# miranda_hector_115clock-6.net
KiCad netlist of a schematic drawn in EAGLE
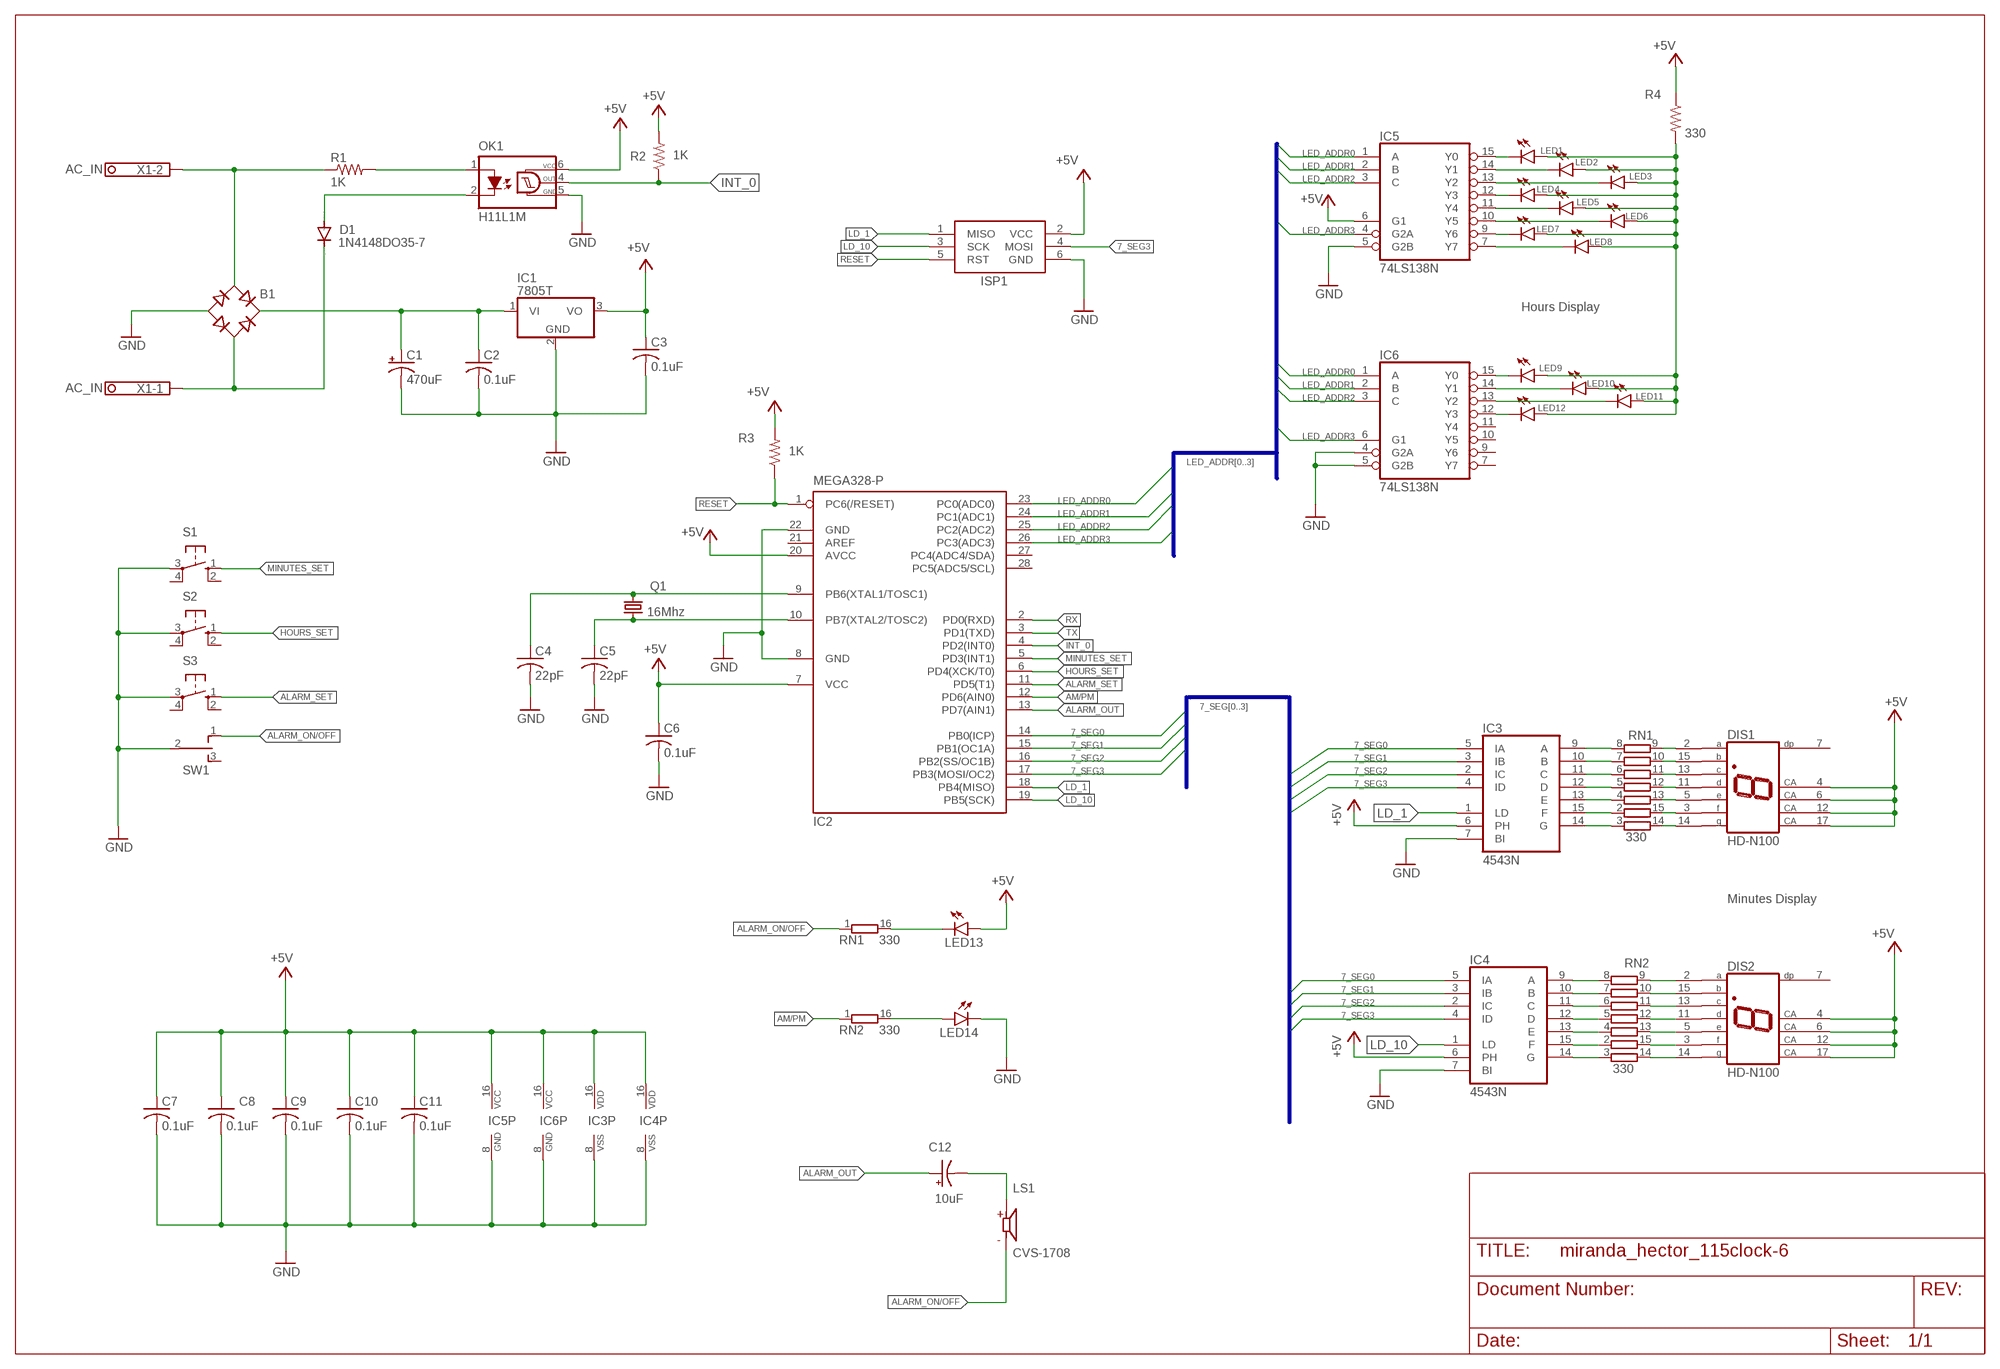
[diagram p0: schematic, sheet 1]

(export (version "E")
  (design (tool "Eeschema 10.0.6"))
  (components
    (comp (ref "B1")
      (value "B-DIL")
      (footprint "eagle-import:B-DIL")
      (libsource (lib "eagle-import") (part "B-DIL"))
    )
    (comp (ref "C1")
      (value "470uF")
      (footprint "eagle-import:E3,5-8")
      (libsource (lib "eagle-import") (part "CPOL-USE3.5-8"))
    )
    (comp (ref "C2")
      (value "0.1uF")
      (footprint "eagle-import:C025-025X050")
      (libsource (lib "eagle-import") (part "C-US025-025X050"))
    )
    (comp (ref "C3")
      (value "0.1uF")
      (footprint "eagle-import:C025-025X050")
      (libsource (lib "eagle-import") (part "C-US025-025X050"))
    )
    (comp (ref "C4")
      (value "22pF")
      (footprint "eagle-import:C025-025X050")
      (libsource (lib "eagle-import") (part "C-US025-025X050"))
    )
    (comp (ref "C5")
      (value "22pF")
      (footprint "eagle-import:C025-025X050")
      (libsource (lib "eagle-import") (part "C-US025-025X050"))
    )
    (comp (ref "C6")
      (value "0.1uF")
      (footprint "eagle-import:C025-025X050")
      (libsource (lib "eagle-import") (part "C-US025-025X050"))
    )
    (comp (ref "C7")
      (value "0.1uF")
      (footprint "eagle-import:C025-025X050")
      (libsource (lib "eagle-import") (part "C-US025-025X050"))
    )
    (comp (ref "C8")
      (value "0.1uF")
      (footprint "eagle-import:C025-025X050")
      (libsource (lib "eagle-import") (part "C-US025-025X050"))
    )
    (comp (ref "C9")
      (value "0.1uF")
      (footprint "eagle-import:C025-025X050")
      (libsource (lib "eagle-import") (part "C-US025-025X050"))
    )
    (comp (ref "C10")
      (value "0.1uF")
      (footprint "eagle-import:C025-025X050")
      (libsource (lib "eagle-import") (part "C-US025-025X050"))
    )
    (comp (ref "C11")
      (value "0.1uF")
      (footprint "eagle-import:C025-025X050")
      (libsource (lib "eagle-import") (part "C-US025-025X050"))
    )
    (comp (ref "C12")
      (value "10uF")
      (footprint "eagle-import:E2,5-6E")
      (libsource (lib "eagle-import") (part "CPOL-USE2,5-6E"))
    )
    (comp (ref "D1")
      (value "1N4148DO35-7")
      (footprint "eagle-import:DO35-7")
      (libsource (lib "eagle-import") (part "1N4148DO35-7"))
    )
    (comp (ref "DIS1")
      (value "HD-N100")
      (footprint "eagle-import:HDSP-Q")
      (libsource (lib "eagle-import") (part "HD-N100"))
    )
    (comp (ref "DIS2")
      (value "HD-N100")
      (footprint "eagle-import:HDSP-Q")
      (libsource (lib "eagle-import") (part "HD-N100"))
    )
    (comp (ref "IC1")
      (value "7805T")
      (footprint "eagle-import:TO220H")
      (libsource (lib "eagle-import") (part "78T05"))
    )
    (comp (ref "IC2")
      (value "MEGA328-P")
      (footprint "eagle-import:DIL28-3")
      (libsource (lib "eagle-import") (part "MEGA8-P"))
    )
    (comp (ref "IC3")
      (value "4543N")
      (footprint "eagle-import:DIL16")
      (libsource (lib "eagle-import") (part "4543N"))
    )
    (comp (ref "IC4")
      (value "4543N")
      (footprint "eagle-import:DIL16")
      (libsource (lib "eagle-import") (part "4543N"))
    )
    (comp (ref "IC5")
      (value "74LS138N")
      (footprint "eagle-import:DIL16")
      (libsource (lib "eagle-import") (part "74138NLS"))
    )
    (comp (ref "IC6")
      (value "74LS138N")
      (footprint "eagle-import:DIL16")
      (libsource (lib "eagle-import") (part "74138NLS"))
    )
    (comp (ref "ISP1")
      (value "AVRISP-6")
      (footprint "eagle-import:AVRISP")
      (libsource (lib "eagle-import") (part "AVRISP-6"))
    )
    (comp (ref "LED1")
      (value "LED10MM")
      (footprint "eagle-import:LED10MM")
      (libsource (lib "eagle-import") (part "LED10MM"))
    )
    (comp (ref "LED2")
      (value "LED10MM")
      (footprint "eagle-import:LED10MM")
      (libsource (lib "eagle-import") (part "LED10MM"))
    )
    (comp (ref "LED3")
      (value "LED10MM")
      (footprint "eagle-import:LED10MM")
      (libsource (lib "eagle-import") (part "LED10MM"))
    )
    (comp (ref "LED4")
      (value "LED10MM")
      (footprint "eagle-import:LED10MM")
      (libsource (lib "eagle-import") (part "LED10MM"))
    )
    (comp (ref "LED5")
      (value "LED10MM")
      (footprint "eagle-import:LED10MM")
      (libsource (lib "eagle-import") (part "LED10MM"))
    )
    (comp (ref "LED6")
      (value "LED10MM")
      (footprint "eagle-import:LED10MM")
      (libsource (lib "eagle-import") (part "LED10MM"))
    )
    (comp (ref "LED7")
      (value "LED10MM")
      (footprint "eagle-import:LED10MM")
      (libsource (lib "eagle-import") (part "LED10MM"))
    )
    (comp (ref "LED8")
      (value "LED10MM")
      (footprint "eagle-import:LED10MM")
      (libsource (lib "eagle-import") (part "LED10MM"))
    )
    (comp (ref "LED9")
      (value "LED10MM")
      (footprint "eagle-import:LED10MM")
      (libsource (lib "eagle-import") (part "LED10MM"))
    )
    (comp (ref "LED10")
      (value "LED10MM")
      (footprint "eagle-import:LED10MM")
      (libsource (lib "eagle-import") (part "LED10MM"))
    )
    (comp (ref "LED11")
      (value "LED10MM")
      (footprint "eagle-import:LED10MM")
      (libsource (lib "eagle-import") (part "LED10MM"))
    )
    (comp (ref "LED12")
      (value "LED10MM")
      (footprint "eagle-import:LED10MM")
      (libsource (lib "eagle-import") (part "LED10MM"))
    )
    (comp (ref "LED13")
      (value "LED5MM")
      (footprint "eagle-import:LED5MM")
      (libsource (lib "eagle-import") (part "LED5MM"))
    )
    (comp (ref "LED14")
      (value "LED5MM")
      (footprint "eagle-import:LED5MM")
      (libsource (lib "eagle-import") (part "LED5MM"))
    )
    (comp (ref "LS1")
      (value "CVS-1708")
      (footprint "eagle-import:SPKR_CVS-1708")
      (fields (field (name "MF") "CUI"))
      (libsource (lib "eagle-import") (part "CVS-1708"))
    )
    (comp (ref "OK1")
      (value "H11L1M")
      (footprint "eagle-import:DIL06")
      (fields (field (name "MF") "FAIRCHILD SEMICONDUCTOR") (field (name "MPN") "H11L1-M"))
      (libsource (lib "eagle-import") (part "H11LM1"))
    )
    (comp (ref "Q1")
      (value "16Mhz")
      (footprint "eagle-import:HC49_S")
      (libsource (lib "eagle-import") (part "CRYSTALHC49S"))
    )
    (comp (ref "R1")
      (value "1K")
      (footprint "eagle-import:0204_7")
      (libsource (lib "eagle-import") (part "R-US_0204/7"))
    )
    (comp (ref "R2")
      (value "1K")
      (footprint "eagle-import:0204_7")
      (libsource (lib "eagle-import") (part "R-US_0204/7"))
    )
    (comp (ref "R3")
      (value "1K")
      (footprint "eagle-import:0204_7")
      (libsource (lib "eagle-import") (part "R-US_0204/7"))
    )
    (comp (ref "R4")
      (value "330")
      (footprint "eagle-import:0204_7")
      (libsource (lib "eagle-import") (part "R-US_0204/7"))
    )
    (comp (ref "RN1")
      (value "330")
      (footprint "eagle-import:DIL16")
      (libsource (lib "eagle-import") (part "8R-P"))
    )
    (comp (ref "RN2")
      (value "330")
      (footprint "eagle-import:DIL16")
      (libsource (lib "eagle-import") (part "8R-P"))
    )
    (comp (ref "S1")
      (value "10-XX")
      (footprint "eagle-import:B3F-10XX")
      (fields (field (name "MPN") "B3F-1000"))
      (libsource (lib "eagle-import") (part "10-XX"))
    )
    (comp (ref "S2")
      (value "10-XX")
      (footprint "eagle-import:B3F-10XX")
      (fields (field (name "MPN") "B3F-1000"))
      (libsource (lib "eagle-import") (part "10-XX"))
    )
    (comp (ref "S3")
      (value "10-XX")
      (footprint "eagle-import:B3F-10XX")
      (fields (field (name "MPN") "B3F-1000"))
      (libsource (lib "eagle-import") (part "10-XX"))
    )
    (comp (ref "SW1")
      (value "DIGICLOCK_S5")
      (footprint "eagle-import:FOOTPRINT_DIGICLOCK_S5")
      (libsource (lib "eagle-import") (part "DIGICLOCK_S5"))
    )
    (comp (ref "X1")
      (value "1751248")
      (footprint "eagle-import:1751248")
      (libsource (lib "eagle-import") (part "1751248"))
    )
  )
  (nets
    (net (code "1") (name "+5V") (class "Default")
      (node (ref "C10") (pin "1") (pinfunction "1_1") (pintype "passive"))
      (node (ref "C11") (pin "1") (pinfunction "1_1") (pintype "passive"))
      (node (ref "C3") (pin "1") (pinfunction "1_1") (pintype "passive"))
      (node (ref "C6") (pin "1") (pinfunction "1_1") (pintype "passive"))
      (node (ref "C7") (pin "1") (pinfunction "1_1") (pintype "passive"))
      (node (ref "C8") (pin "1") (pinfunction "1_1") (pintype "passive"))
      (node (ref "C9") (pin "1") (pinfunction "1_1") (pintype "passive"))
      (node (ref "DIS1") (pin "12") (pinfunction "CA_12") (pintype "passive"))
      (node (ref "DIS1") (pin "17") (pinfunction "CA_17") (pintype "passive"))
      (node (ref "DIS1") (pin "4") (pinfunction "CA_4") (pintype "passive"))
      (node (ref "DIS1") (pin "6") (pinfunction "CA_6") (pintype "passive"))
      (node (ref "DIS2") (pin "12") (pinfunction "CA_12") (pintype "passive"))
      (node (ref "DIS2") (pin "17") (pinfunction "CA_17") (pintype "passive"))
      (node (ref "DIS2") (pin "4") (pinfunction "CA_4") (pintype "passive"))
      (node (ref "DIS2") (pin "6") (pinfunction "CA_6") (pintype "passive"))
      (node (ref "IC1") (pin "3") (pinfunction "VO_3") (pintype "passive"))
      (node (ref "IC2") (pin "20") (pinfunction "AVCC_20") (pintype "power_in"))
      (node (ref "IC2") (pin "7") (pinfunction "VCC_7") (pintype "power_in"))
      (node (ref "IC3") (pin "16") (pinfunction "VDD_16") (pintype "power_in"))
      (node (ref "IC3") (pin "6") (pinfunction "PH_6") (pintype "input"))
      (node (ref "IC4") (pin "16") (pinfunction "VDD_16") (pintype "power_in"))
      (node (ref "IC4") (pin "6") (pinfunction "PH_6") (pintype "input"))
      (node (ref "IC5") (pin "16") (pinfunction "VCC_16") (pintype "power_in"))
      (node (ref "IC5") (pin "6") (pinfunction "G1_6") (pintype "input"))
      (node (ref "IC6") (pin "16") (pinfunction "VCC_16") (pintype "power_in"))
      (node (ref "ISP1") (pin "2") (pinfunction "VCC_2") (pintype "power_in"))
      (node (ref "LED13") (pin "A") (pinfunction "A_A") (pintype "passive"))
      (node (ref "OK1") (pin "6") (pinfunction "VCC_6") (pintype "power_in"))
      (node (ref "R2") (pin "2") (pinfunction "2_2") (pintype "passive"))
      (node (ref "R3") (pin "2") (pinfunction "2_2") (pintype "passive"))
      (node (ref "R4") (pin "1") (pinfunction "1_1") (pintype "passive"))
    )
    (net (code "2") (name "/7_SEG0") (class "Default")
      (node (ref "IC2") (pin "14") (pinfunction "PB0(ICP)_14") (pintype "bidirectional"))
      (node (ref "IC3") (pin "5") (pinfunction "IA_5") (pintype "input"))
      (node (ref "IC4") (pin "5") (pinfunction "IA_5") (pintype "input"))
    )
    (net (code "3") (name "/7_SEG1") (class "Default")
      (node (ref "IC2") (pin "15") (pinfunction "PB1(OC1A)_15") (pintype "bidirectional"))
      (node (ref "IC3") (pin "3") (pinfunction "IB_3") (pintype "input"))
      (node (ref "IC4") (pin "3") (pinfunction "IB_3") (pintype "input"))
    )
    (net (code "4") (name "/7_SEG2") (class "Default")
      (node (ref "IC2") (pin "16") (pinfunction "PB2(SS/OC1B)_16") (pintype "bidirectional"))
      (node (ref "IC3") (pin "2") (pinfunction "IC_2") (pintype "input"))
      (node (ref "IC4") (pin "2") (pinfunction "IC_2") (pintype "input"))
    )
    (net (code "6") (name "/LED_ADDR0") (class "Default")
      (node (ref "IC2") (pin "23") (pinfunction "PC0(ADC0)_23") (pintype "bidirectional"))
      (node (ref "IC5") (pin "1") (pinfunction "A_1") (pintype "input"))
      (node (ref "IC6") (pin "1") (pinfunction "A_1") (pintype "input"))
    )
    (net (code "7") (name "/LED_ADDR1") (class "Default")
      (node (ref "IC2") (pin "24") (pinfunction "PC1(ADC1)_24") (pintype "bidirectional"))
      (node (ref "IC5") (pin "2") (pinfunction "B_2") (pintype "input"))
      (node (ref "IC6") (pin "2") (pinfunction "B_2") (pintype "input"))
    )
    (net (code "8") (name "/LED_ADDR2") (class "Default")
      (node (ref "IC2") (pin "25") (pinfunction "PC2(ADC2)_25") (pintype "bidirectional"))
      (node (ref "IC5") (pin "3") (pinfunction "C_3") (pintype "input"))
      (node (ref "IC6") (pin "3") (pinfunction "C_3") (pintype "input"))
    )
    (net (code "9") (name "/LED_ADDR3") (class "Default")
      (node (ref "IC2") (pin "26") (pinfunction "PC3(ADC3)_26") (pintype "bidirectional"))
      (node (ref "IC5") (pin "4") (pinfunction "G2A_4") (pintype "input"))
      (node (ref "IC6") (pin "6") (pinfunction "G1_6") (pintype "input"))
    )
    (net (code "11") (name "7_SEG3") (class "Default")
      (node (ref "IC2") (pin "17") (pinfunction "PB3(MOSI/OC2)_17") (pintype "bidirectional"))
      (node (ref "IC3") (pin "4") (pinfunction "ID_4") (pintype "input"))
      (node (ref "IC4") (pin "4") (pinfunction "ID_4") (pintype "input"))
      (node (ref "ISP1") (pin "4") (pinfunction "MOSI_4") (pintype "output"))
    )
    (net (code "12") (name "ALARM_ON{slash}OFF") (class "Default")
      (node (ref "LS1") (pin "M") (pinfunction "M_M") (pintype "passive"))
      (node (ref "RN1") (pin "1") (pinfunction "1_1") (pintype "passive"))
      (node (ref "SW1") (pin "1") (pinfunction "O_1") (pintype "passive"))
    )
    (net (code "13") (name "ALARM_OUT") (class "Default")
      (node (ref "C12") (pin "+") (pinfunction "+_+") (pintype "passive"))
      (node (ref "IC2") (pin "13") (pinfunction "PD7(AIN1)_13") (pintype "bidirectional"))
    )
    (net (code "14") (name "ALARM_SET") (class "Default")
      (node (ref "IC2") (pin "11") (pinfunction "PD5(T1)_11") (pintype "bidirectional"))
      (node (ref "S3") (pin "1") (pinfunction "S_1") (pintype "passive"))
    )
    (net (code "15") (name "AM{slash}PM") (class "Default")
      (node (ref "IC2") (pin "12") (pinfunction "PD6(AIN0)_12") (pintype "bidirectional"))
      (node (ref "RN2") (pin "1") (pinfunction "1_1") (pintype "passive"))
    )
    (net (code "16") (name "GND") (class "Default")
      (node (ref "B1") (pin "-") (pinfunction "-_-") (pintype "passive"))
      (node (ref "C1") (pin "-") (pinfunction "-_-") (pintype "passive"))
      (node (ref "C10") (pin "2") (pinfunction "2_2") (pintype "passive"))
      (node (ref "C11") (pin "2") (pinfunction "2_2") (pintype "passive"))
      (node (ref "C2") (pin "2") (pinfunction "2_2") (pintype "passive"))
      (node (ref "C3") (pin "2") (pinfunction "2_2") (pintype "passive"))
      (node (ref "C4") (pin "2") (pinfunction "2_2") (pintype "passive"))
      (node (ref "C5") (pin "2") (pinfunction "2_2") (pintype "passive"))
      (node (ref "C6") (pin "2") (pinfunction "2_2") (pintype "passive"))
      (node (ref "C7") (pin "2") (pinfunction "2_2") (pintype "passive"))
      (node (ref "C8") (pin "2") (pinfunction "2_2") (pintype "passive"))
      (node (ref "C9") (pin "2") (pinfunction "2_2") (pintype "passive"))
      (node (ref "IC1") (pin "2") (pinfunction "GND_2") (pintype "passive"))
      (node (ref "IC2") (pin "22") (pinfunction "GND_22") (pintype "power_in"))
      (node (ref "IC2") (pin "8") (pinfunction "GND_8") (pintype "power_in"))
      (node (ref "IC3") (pin "7") (pinfunction "BI_7") (pintype "input"))
      (node (ref "IC3") (pin "8") (pinfunction "VSS_8") (pintype "power_in"))
      (node (ref "IC4") (pin "7") (pinfunction "BI_7") (pintype "input"))
      (node (ref "IC4") (pin "8") (pinfunction "VSS_8") (pintype "power_in"))
      (node (ref "IC5") (pin "5") (pinfunction "G2B_5") (pintype "input"))
      (node (ref "IC5") (pin "8") (pinfunction "GND_8") (pintype "power_in"))
      (node (ref "IC6") (pin "4") (pinfunction "G2A_4") (pintype "input"))
      (node (ref "IC6") (pin "5") (pinfunction "G2B_5") (pintype "input"))
      (node (ref "IC6") (pin "8") (pinfunction "GND_8") (pintype "power_in"))
      (node (ref "ISP1") (pin "6") (pinfunction "GND_6") (pintype "power_in"))
      (node (ref "LED14") (pin "K") (pinfunction "C_K") (pintype "passive"))
      (node (ref "OK1") (pin "5") (pinfunction "GND_5") (pintype "power_in"))
      (node (ref "S1") (pin "3") (pinfunction "P_3") (pintype "passive"))
      (node (ref "S2") (pin "3") (pinfunction "P_3") (pintype "passive"))
      (node (ref "S3") (pin "3") (pinfunction "P_3") (pintype "passive"))
      (node (ref "SW1") (pin "2") (pinfunction "P_2") (pintype "passive"))
    )
    (net (code "17") (name "HOURS_SET") (class "Default")
      (node (ref "IC2") (pin "6") (pinfunction "PD4(XCK/T0)_6") (pintype "bidirectional"))
      (node (ref "S2") (pin "1") (pinfunction "S_1") (pintype "passive"))
    )
    (net (code "18") (name "INT_0") (class "Default")
      (node (ref "IC2") (pin "4") (pinfunction "PD2(INT0)_4") (pintype "bidirectional"))
      (node (ref "OK1") (pin "4") (pinfunction "OUT_4") (pintype "output"))
      (node (ref "R2") (pin "1") (pinfunction "1_1") (pintype "passive"))
    )
    (net (code "19") (name "LD_1") (class "Default")
      (node (ref "IC2") (pin "18") (pinfunction "PB4(MISO)_18") (pintype "bidirectional"))
      (node (ref "IC3") (pin "1") (pinfunction "LD_1") (pintype "input"))
      (node (ref "ISP1") (pin "1") (pinfunction "MISO_1") (pintype "input"))
    )
    (net (code "20") (name "LD_10") (class "Default")
      (node (ref "IC2") (pin "19") (pinfunction "PB5(SCK)_19") (pintype "bidirectional"))
      (node (ref "IC4") (pin "1") (pinfunction "LD_1") (pintype "input"))
      (node (ref "ISP1") (pin "3") (pinfunction "SCK_3") (pintype "output"))
    )
    (net (code "21") (name "MINUTES_SET") (class "Default")
      (node (ref "IC2") (pin "5") (pinfunction "PD3(INT1)_5") (pintype "bidirectional"))
      (node (ref "S1") (pin "1") (pinfunction "S_1") (pintype "passive"))
    )
    (net (code "22") (name "Net-(C12-Pad-)") (class "Default")
      (node (ref "C12") (pin "-") (pinfunction "-_-") (pintype "passive"))
      (node (ref "LS1") (pin "P") (pinfunction "P_P") (pintype "passive"))
    )
    (net (code "23") (name "Net-(DIS1-A)") (class "Default")
      (node (ref "DIS1") (pin "2") (pinfunction "A_2") (pintype "passive"))
      (node (ref "RN1") (pin "9") (pinfunction "2_9") (pintype "passive"))
    )
    (net (code "24") (name "Net-(DIS1-B)") (class "Default")
      (node (ref "DIS1") (pin "15") (pinfunction "B_15") (pintype "passive"))
      (node (ref "RN1") (pin "10") (pinfunction "2_10") (pintype "passive"))
    )
    (net (code "25") (name "Net-(DIS1-C)") (class "Default")
      (node (ref "DIS1") (pin "13") (pinfunction "C_13") (pintype "passive"))
      (node (ref "RN1") (pin "11") (pinfunction "2_11") (pintype "passive"))
    )
    (net (code "26") (name "Net-(DIS1-D)") (class "Default")
      (node (ref "DIS1") (pin "11") (pinfunction "D_11") (pintype "passive"))
      (node (ref "RN1") (pin "12") (pinfunction "2_12") (pintype "passive"))
    )
    (net (code "27") (name "Net-(DIS1-E)") (class "Default")
      (node (ref "DIS1") (pin "5") (pinfunction "E_5") (pintype "passive"))
      (node (ref "RN1") (pin "13") (pinfunction "2_13") (pintype "passive"))
    )
    (net (code "28") (name "Net-(DIS1-F)") (class "Default")
      (node (ref "DIS1") (pin "3") (pinfunction "F_3") (pintype "passive"))
      (node (ref "RN1") (pin "15") (pinfunction "2_15") (pintype "passive"))
    )
    (net (code "29") (name "Net-(DIS1-G)") (class "Default")
      (node (ref "DIS1") (pin "14") (pinfunction "G_14") (pintype "passive"))
      (node (ref "RN1") (pin "14") (pinfunction "2_14") (pintype "passive"))
    )
    (net (code "30") (name "Net-(DIS2-A)") (class "Default")
      (node (ref "DIS2") (pin "2") (pinfunction "A_2") (pintype "passive"))
      (node (ref "RN2") (pin "9") (pinfunction "2_9") (pintype "passive"))
    )
    (net (code "31") (name "Net-(DIS2-B)") (class "Default")
      (node (ref "DIS2") (pin "15") (pinfunction "B_15") (pintype "passive"))
      (node (ref "RN2") (pin "10") (pinfunction "2_10") (pintype "passive"))
    )
    (net (code "32") (name "Net-(DIS2-C)") (class "Default")
      (node (ref "DIS2") (pin "13") (pinfunction "C_13") (pintype "passive"))
      (node (ref "RN2") (pin "11") (pinfunction "2_11") (pintype "passive"))
    )
    (net (code "33") (name "Net-(DIS2-D)") (class "Default")
      (node (ref "DIS2") (pin "11") (pinfunction "D_11") (pintype "passive"))
      (node (ref "RN2") (pin "12") (pinfunction "2_12") (pintype "passive"))
    )
    (net (code "34") (name "Net-(DIS2-E)") (class "Default")
      (node (ref "DIS2") (pin "5") (pinfunction "E_5") (pintype "passive"))
      (node (ref "RN2") (pin "13") (pinfunction "2_13") (pintype "passive"))
    )
    (net (code "35") (name "Net-(DIS2-F)") (class "Default")
      (node (ref "DIS2") (pin "3") (pinfunction "F_3") (pintype "passive"))
      (node (ref "RN2") (pin "15") (pinfunction "2_15") (pintype "passive"))
    )
    (net (code "36") (name "Net-(DIS2-G)") (class "Default")
      (node (ref "DIS2") (pin "14") (pinfunction "G_14") (pintype "passive"))
      (node (ref "RN2") (pin "14") (pinfunction "2_14") (pintype "passive"))
    )
    (net (code "37") (name "Net-(IC1-VI)") (class "Default")
      (node (ref "B1") (pin "+") (pinfunction "+_+") (pintype "passive"))
      (node (ref "C1") (pin "+") (pinfunction "+_+") (pintype "passive"))
      (node (ref "C2") (pin "1") (pinfunction "1_1") (pintype "passive"))
      (node (ref "IC1") (pin "1") (pinfunction "VI_1") (pintype "input"))
    )
    (net (code "38") (name "Net-(IC2-PB6(XTAL1{slash}TOSC1))") (class "Default")
      (node (ref "C4") (pin "1") (pinfunction "1_1") (pintype "passive"))
      (node (ref "IC2") (pin "9") (pinfunction "PB6(XTAL1/TOSC1)_9") (pintype "bidirectional"))
      (node (ref "Q1") (pin "2") (pinfunction "2_2") (pintype "passive"))
    )
    (net (code "39") (name "Net-(IC2-PB7(XTAL2{slash}TOSC2))") (class "Default")
      (node (ref "C5") (pin "1") (pinfunction "1_1") (pintype "passive"))
      (node (ref "IC2") (pin "10") (pinfunction "PB7(XTAL2/TOSC2)_10") (pintype "bidirectional"))
      (node (ref "Q1") (pin "1") (pinfunction "1_1") (pintype "passive"))
    )
    (net (code "40") (name "Net-(IC3A-A)") (class "Default")
      (node (ref "IC3") (pin "9") (pinfunction "A_9") (pintype "output"))
      (node (ref "RN1") (pin "8") (pinfunction "1_8") (pintype "passive"))
    )
    (net (code "41") (name "Net-(IC3A-B)") (class "Default")
      (node (ref "IC3") (pin "10") (pinfunction "B_10") (pintype "output"))
      (node (ref "RN1") (pin "7") (pinfunction "1_7") (pintype "passive"))
    )
    (net (code "42") (name "Net-(IC3A-C)") (class "Default")
      (node (ref "IC3") (pin "11") (pinfunction "C_11") (pintype "output"))
      (node (ref "RN1") (pin "6") (pinfunction "1_6") (pintype "passive"))
    )
    (net (code "43") (name "Net-(IC3A-D)") (class "Default")
      (node (ref "IC3") (pin "12") (pinfunction "D_12") (pintype "output"))
      (node (ref "RN1") (pin "5") (pinfunction "1_5") (pintype "passive"))
    )
    (net (code "44") (name "Net-(IC3A-E)") (class "Default")
      (node (ref "IC3") (pin "13") (pinfunction "E_13") (pintype "output"))
      (node (ref "RN1") (pin "4") (pinfunction "1_4") (pintype "passive"))
    )
    (net (code "45") (name "Net-(IC3A-F)") (class "Default")
      (node (ref "IC3") (pin "15") (pinfunction "F_15") (pintype "output"))
      (node (ref "RN1") (pin "2") (pinfunction "1_2") (pintype "passive"))
    )
    (net (code "46") (name "Net-(IC3A-G)") (class "Default")
      (node (ref "IC3") (pin "14") (pinfunction "G_14") (pintype "output"))
      (node (ref "RN1") (pin "3") (pinfunction "1_3") (pintype "passive"))
    )
    (net (code "47") (name "Net-(IC4A-A)") (class "Default")
      (node (ref "IC4") (pin "9") (pinfunction "A_9") (pintype "output"))
      (node (ref "RN2") (pin "8") (pinfunction "1_8") (pintype "passive"))
    )
    (net (code "48") (name "Net-(IC4A-B)") (class "Default")
      (node (ref "IC4") (pin "10") (pinfunction "B_10") (pintype "output"))
      (node (ref "RN2") (pin "7") (pinfunction "1_7") (pintype "passive"))
    )
    (net (code "49") (name "Net-(IC4A-C)") (class "Default")
      (node (ref "IC4") (pin "11") (pinfunction "C_11") (pintype "output"))
      (node (ref "RN2") (pin "6") (pinfunction "1_6") (pintype "passive"))
    )
    (net (code "50") (name "Net-(IC4A-D)") (class "Default")
      (node (ref "IC4") (pin "12") (pinfunction "D_12") (pintype "output"))
      (node (ref "RN2") (pin "5") (pinfunction "1_5") (pintype "passive"))
    )
    (net (code "51") (name "Net-(IC4A-E)") (class "Default")
      (node (ref "IC4") (pin "13") (pinfunction "E_13") (pintype "output"))
      (node (ref "RN2") (pin "4") (pinfunction "1_4") (pintype "passive"))
    )
    (net (code "52") (name "Net-(IC4A-F)") (class "Default")
      (node (ref "IC4") (pin "15") (pinfunction "F_15") (pintype "output"))
      (node (ref "RN2") (pin "2") (pinfunction "1_2") (pintype "passive"))
    )
    (net (code "53") (name "Net-(IC4A-G)") (class "Default")
      (node (ref "IC4") (pin "14") (pinfunction "G_14") (pintype "output"))
      (node (ref "RN2") (pin "3") (pinfunction "1_3") (pintype "passive"))
    )
    (net (code "54") (name "Net-(IC5A-Y0)") (class "Default")
      (node (ref "IC5") (pin "15") (pinfunction "Y0_15") (pintype "output"))
      (node (ref "LED1") (pin "K") (pinfunction "C_K") (pintype "passive"))
    )
    (net (code "55") (name "Net-(IC5A-Y1)") (class "Default")
      (node (ref "IC5") (pin "14") (pinfunction "Y1_14") (pintype "output"))
      (node (ref "LED2") (pin "K") (pinfunction "C_K") (pintype "passive"))
    )
    (net (code "56") (name "Net-(IC5A-Y2)") (class "Default")
      (node (ref "IC5") (pin "13") (pinfunction "Y2_13") (pintype "output"))
      (node (ref "LED3") (pin "K") (pinfunction "C_K") (pintype "passive"))
    )
    (net (code "57") (name "Net-(IC5A-Y3)") (class "Default")
      (node (ref "IC5") (pin "12") (pinfunction "Y3_12") (pintype "output"))
      (node (ref "LED4") (pin "K") (pinfunction "C_K") (pintype "passive"))
    )
    (net (code "58") (name "Net-(IC5A-Y4)") (class "Default")
      (node (ref "IC5") (pin "11") (pinfunction "Y4_11") (pintype "output"))
      (node (ref "LED5") (pin "K") (pinfunction "C_K") (pintype "passive"))
    )
    (net (code "59") (name "Net-(IC5A-Y5)") (class "Default")
      (node (ref "IC5") (pin "10") (pinfunction "Y5_10") (pintype "output"))
      (node (ref "LED6") (pin "K") (pinfunction "C_K") (pintype "passive"))
    )
    (net (code "60") (name "Net-(IC5A-Y6)") (class "Default")
      (node (ref "IC5") (pin "9") (pinfunction "Y6_9") (pintype "output"))
      (node (ref "LED7") (pin "K") (pinfunction "C_K") (pintype "passive"))
    )
    (net (code "61") (name "Net-(IC5A-Y7)") (class "Default")
      (node (ref "IC5") (pin "7") (pinfunction "Y7_7") (pintype "output"))
      (node (ref "LED8") (pin "K") (pinfunction "C_K") (pintype "passive"))
    )
    (net (code "62") (name "Net-(IC6A-Y0)") (class "Default")
      (node (ref "IC6") (pin "15") (pinfunction "Y0_15") (pintype "output"))
      (node (ref "LED9") (pin "K") (pinfunction "C_K") (pintype "passive"))
    )
    (net (code "63") (name "Net-(IC6A-Y1)") (class "Default")
      (node (ref "IC6") (pin "14") (pinfunction "Y1_14") (pintype "output"))
      (node (ref "LED10") (pin "K") (pinfunction "C_K") (pintype "passive"))
    )
    (net (code "64") (name "Net-(IC6A-Y2)") (class "Default")
      (node (ref "IC6") (pin "13") (pinfunction "Y2_13") (pintype "output"))
      (node (ref "LED11") (pin "K") (pinfunction "C_K") (pintype "passive"))
    )
    (net (code "65") (name "Net-(IC6A-Y3)") (class "Default")
      (node (ref "IC6") (pin "12") (pinfunction "Y3_12") (pintype "output"))
      (node (ref "LED12") (pin "K") (pinfunction "C_K") (pintype "passive"))
    )
    (net (code "66") (name "Net-(LED1-PadA)") (class "Default")
      (node (ref "LED1") (pin "A") (pinfunction "A_A") (pintype "passive"))
      (node (ref "LED10") (pin "A") (pinfunction "A_A") (pintype "passive"))
      (node (ref "LED11") (pin "A") (pinfunction "A_A") (pintype "passive"))
      (node (ref "LED12") (pin "A") (pinfunction "A_A") (pintype "passive"))
      (node (ref "LED2") (pin "A") (pinfunction "A_A") (pintype "passive"))
      (node (ref "LED3") (pin "A") (pinfunction "A_A") (pintype "passive"))
      (node (ref "LED4") (pin "A") (pinfunction "A_A") (pintype "passive"))
      (node (ref "LED5") (pin "A") (pinfunction "A_A") (pintype "passive"))
      (node (ref "LED6") (pin "A") (pinfunction "A_A") (pintype "passive"))
      (node (ref "LED7") (pin "A") (pinfunction "A_A") (pintype "passive"))
      (node (ref "LED8") (pin "A") (pinfunction "A_A") (pintype "passive"))
      (node (ref "LED9") (pin "A") (pinfunction "A_A") (pintype "passive"))
      (node (ref "R4") (pin "2") (pinfunction "2_2") (pintype "passive"))
    )
    (net (code "67") (name "Net-(LED13-C)") (class "Default")
      (node (ref "LED13") (pin "K") (pinfunction "C_K") (pintype "passive"))
      (node (ref "RN1") (pin "16") (pinfunction "2_16") (pintype "passive"))
    )
    (net (code "68") (name "Net-(OK1-A)") (class "Default")
      (node (ref "OK1") (pin "1") (pinfunction "A_1") (pintype "passive"))
      (node (ref "R1") (pin "2") (pinfunction "2_2") (pintype "passive"))
    )
    (net (code "69") (name "Net-(OK1-C)") (class "Default")
      (node (ref "D1") (pin "A") (pinfunction "A_A") (pintype "passive"))
      (node (ref "OK1") (pin "2") (pinfunction "C_2") (pintype "passive"))
    )
    (net (code "70") (name "Net-(RN2A-2)") (class "Default")
      (node (ref "LED14") (pin "A") (pinfunction "A_A") (pintype "passive"))
      (node (ref "RN2") (pin "16") (pinfunction "2_16") (pintype "passive"))
    )
    (net (code "71") (name "Net-(X1A-K)") (class "Default")
      (node (ref "B1") (pin "AC2") (pinfunction "AC2_AC2") (pintype "passive"))
      (node (ref "D1") (pin "C") (pinfunction "C_C") (pintype "passive"))
      (node (ref "X1") (pin "1") (pinfunction "K_1") (pintype "passive"))
    )
    (net (code "72") (name "Net-(X1B-K)") (class "Default")
      (node (ref "B1") (pin "AC1") (pinfunction "AC1_AC1") (pintype "passive"))
      (node (ref "R1") (pin "1") (pinfunction "1_1") (pintype "passive"))
      (node (ref "X1") (pin "2") (pinfunction "K_2") (pintype "passive"))
    )
    (net (code "73") (name "RESET") (class "Default")
      (node (ref "IC2") (pin "1") (pinfunction "PC6(/RESET)_1") (pintype "bidirectional"))
      (node (ref "ISP1") (pin "5") (pinfunction "RST_5") (pintype "output"))
      (node (ref "R3") (pin "1") (pinfunction "1_1") (pintype "passive"))
    )
    (net (code "74") (name "RX") (class "Default")
      (node (ref "IC2") (pin "2") (pinfunction "PD0(RXD)_2") (pintype "bidirectional"))
    )
    (net (code "75") (name "TX") (class "Default")
      (node (ref "IC2") (pin "3") (pinfunction "PD1(TXD)_3") (pintype "bidirectional"))
    )
    (net (code "76") (name "unconnected-(DIS1-DP-Pad7)") (class "Default")
      (node (ref "DIS1") (pin "7") (pinfunction "DP_7") (pintype "passive"))
    )
    (net (code "77") (name "unconnected-(DIS2-DP-Pad7)") (class "Default")
      (node (ref "DIS2") (pin "7") (pinfunction "DP_7") (pintype "passive"))
    )
    (net (code "78") (name "unconnected-(IC2-AREF-Pad21)") (class "Default")
      (node (ref "IC2") (pin "21") (pinfunction "AREF_21") (pintype "passive"))
    )
    (net (code "79") (name "unconnected-(IC2-PC4(ADC4{slash}SDA)-Pad27)") (class "Default")
      (node (ref "IC2") (pin "27") (pinfunction "PC4(ADC4/SDA)_27") (pintype "bidirectional"))
    )
    (net (code "80") (name "unconnected-(IC2-PC5(ADC5{slash}SCL)-Pad28)") (class "Default")
      (node (ref "IC2") (pin "28") (pinfunction "PC5(ADC5/SCL)_28") (pintype "bidirectional"))
    )
    (net (code "81") (name "unconnected-(IC6A-Y4-Pad11)") (class "Default")
      (node (ref "IC6") (pin "11") (pinfunction "Y4_11") (pintype "output"))
    )
    (net (code "82") (name "unconnected-(IC6A-Y5-Pad10)") (class "Default")
      (node (ref "IC6") (pin "10") (pinfunction "Y5_10") (pintype "output"))
    )
    (net (code "83") (name "unconnected-(IC6A-Y6-Pad9)") (class "Default")
      (node (ref "IC6") (pin "9") (pinfunction "Y6_9") (pintype "output"))
    )
    (net (code "84") (name "unconnected-(IC6A-Y7-Pad7)") (class "Default")
      (node (ref "IC6") (pin "7") (pinfunction "Y7_7") (pintype "output"))
    )
    (net (code "85") (name "unconnected-(S1-P1-Pad4)") (class "Default")
      (node (ref "S1") (pin "4") (pinfunction "P1_4") (pintype "passive"))
    )
    (net (code "86") (name "unconnected-(S1-S1-Pad2)") (class "Default")
      (node (ref "S1") (pin "2") (pinfunction "S1_2") (pintype "passive"))
    )
    (net (code "87") (name "unconnected-(S2-P1-Pad4)") (class "Default")
      (node (ref "S2") (pin "4") (pinfunction "P1_4") (pintype "passive"))
    )
    (net (code "88") (name "unconnected-(S2-S1-Pad2)") (class "Default")
      (node (ref "S2") (pin "2") (pinfunction "S1_2") (pintype "passive"))
    )
    (net (code "89") (name "unconnected-(S3-P1-Pad4)") (class "Default")
      (node (ref "S3") (pin "4") (pinfunction "P1_4") (pintype "passive"))
    )
    (net (code "90") (name "unconnected-(S3-S1-Pad2)") (class "Default")
      (node (ref "S3") (pin "2") (pinfunction "S1_2") (pintype "passive"))
    )
    (net (code "91") (name "unconnected-(SW1-S-Pad3)") (class "Default")
      (node (ref "SW1") (pin "3") (pinfunction "S_3") (pintype "passive"))
    )
  )
)
